# IOB-Adapter-Generic.net
KiCad netlist of a schematic drawn in EAGLE
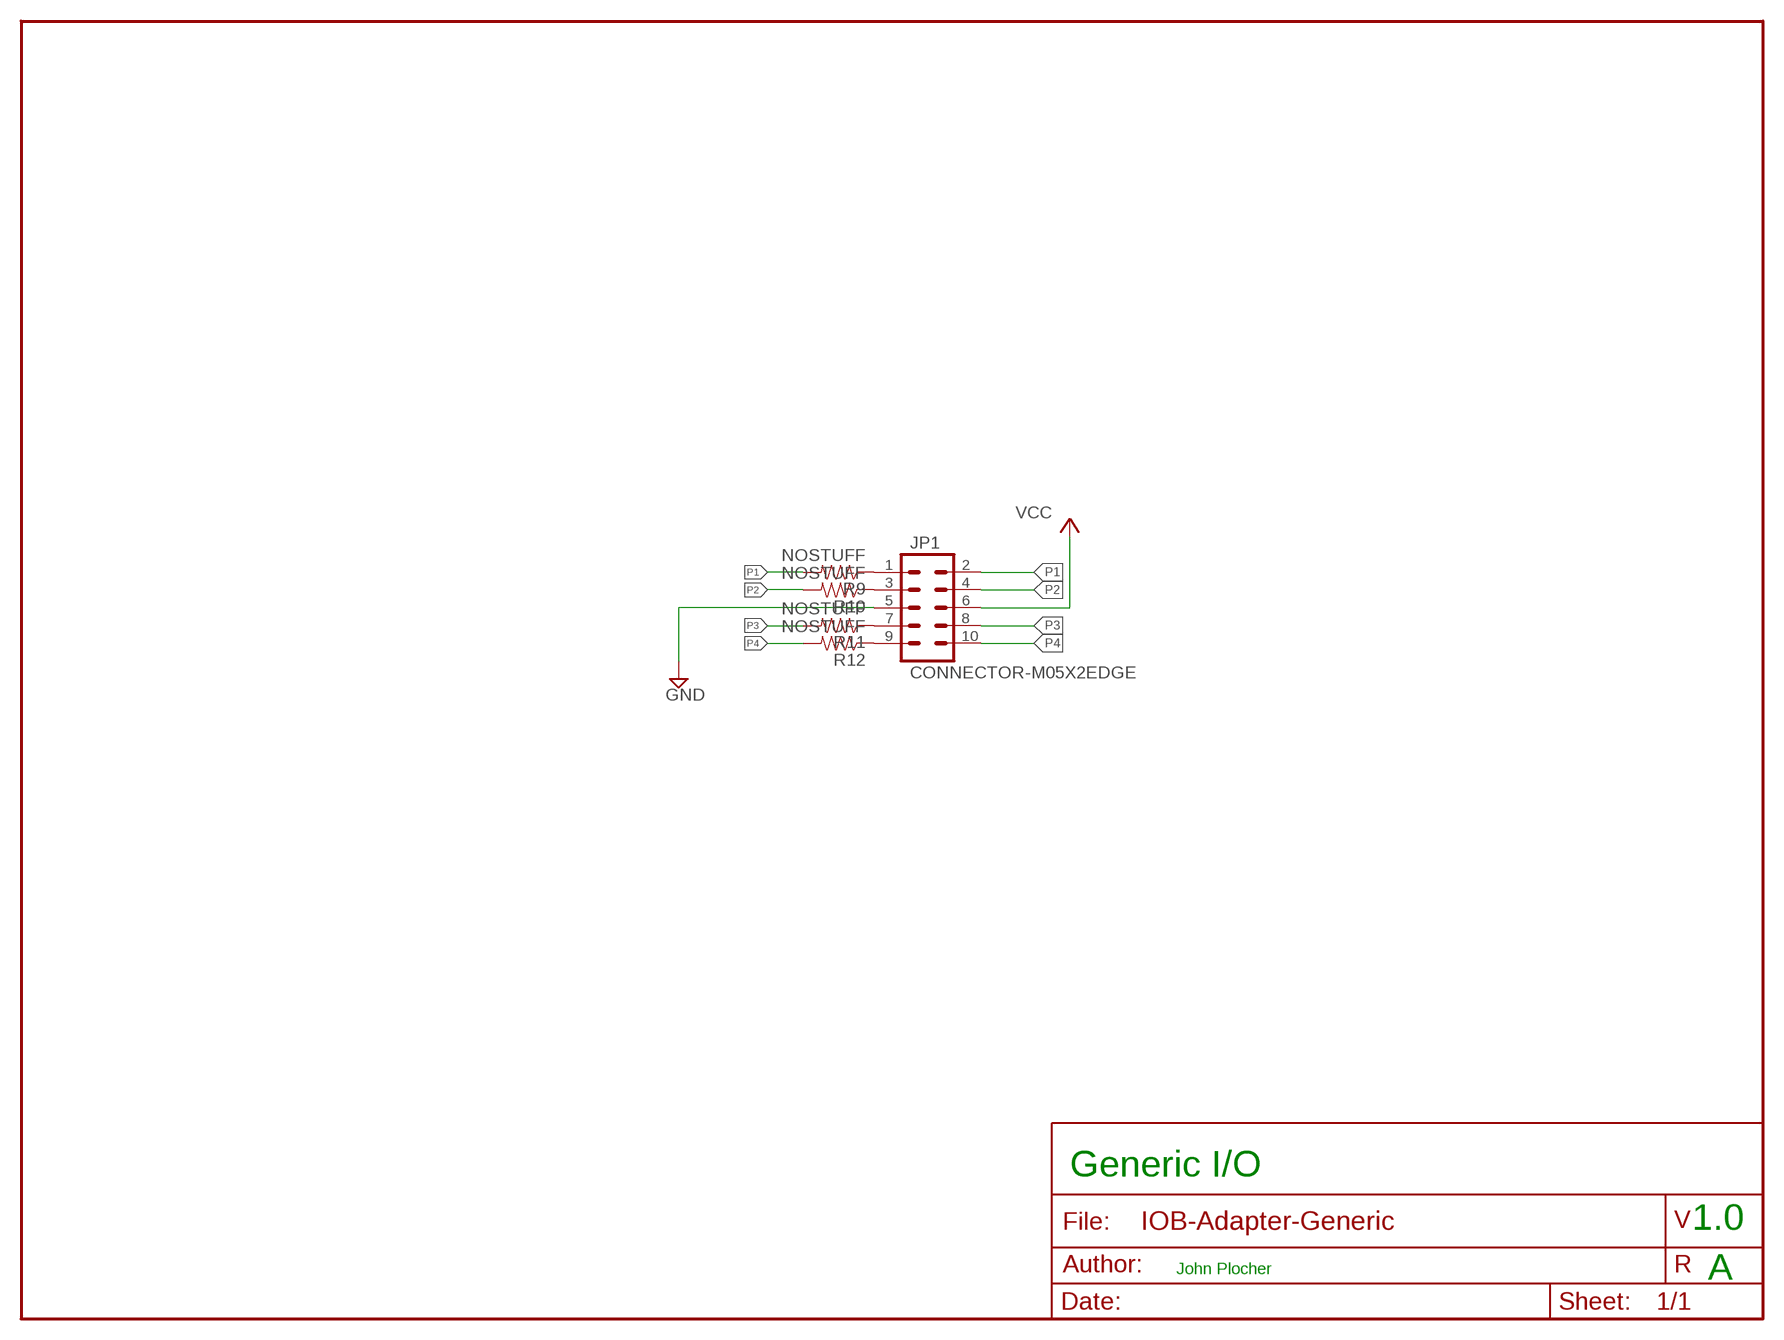
[diagram p0: schematic, sheet 1]

(export (version "E")
  (design (tool "Eeschema 10.0.6"))
  (components
    (comp (ref "JP1")
      (value "CONNECTOR-M05X2EDGE")
      (footprint "eagle-import:2X5-EDGE")
      (libsource (lib "eagle-import") (part "CONNECTOR-M05X2EDGE"))
    )
    (comp (ref "R9")
      (value "NOSTUFF")
      (footprint "eagle-import:CUT-R")
      (libsource (lib "eagle-import") (part "RPTH-R0"))
    )
    (comp (ref "R10")
      (value "NOSTUFF")
      (footprint "eagle-import:CUT-R")
      (libsource (lib "eagle-import") (part "RPTH-R0"))
    )
    (comp (ref "R11")
      (value "NOSTUFF")
      (footprint "eagle-import:CUT-R")
      (libsource (lib "eagle-import") (part "RPTH-R0"))
    )
    (comp (ref "R12")
      (value "NOSTUFF")
      (footprint "eagle-import:CUT-R")
      (libsource (lib "eagle-import") (part "RPTH-R0"))
    )
  )
  (nets
    (net (code "1") (name "GND") (class "Default")
      (node (ref "JP1") (pin "5") (pinfunction "5_5") (pintype "passive"))
    )
    (net (code "2") (name "Net-(R9-1)") (class "Default")
      (node (ref "JP1") (pin "1") (pinfunction "1_1") (pintype "passive"))
      (node (ref "R9") (pin "P2") (pinfunction "1_P2") (pintype "passive"))
    )
    (net (code "3") (name "Net-(R10-1)") (class "Default")
      (node (ref "JP1") (pin "3") (pinfunction "3_3") (pintype "passive"))
      (node (ref "R10") (pin "P2") (pinfunction "1_P2") (pintype "passive"))
    )
    (net (code "4") (name "Net-(R11-1)") (class "Default")
      (node (ref "JP1") (pin "7") (pinfunction "7_7") (pintype "passive"))
      (node (ref "R11") (pin "P2") (pinfunction "1_P2") (pintype "passive"))
    )
    (net (code "5") (name "Net-(R12-1)") (class "Default")
      (node (ref "JP1") (pin "9") (pinfunction "9_9") (pintype "passive"))
      (node (ref "R12") (pin "P2") (pinfunction "1_P2") (pintype "passive"))
    )
    (net (code "6") (name "P1") (class "Default")
      (node (ref "JP1") (pin "2") (pinfunction "2_2") (pintype "passive"))
      (node (ref "R9") (pin "P1") (pinfunction "2_P1") (pintype "passive"))
    )
    (net (code "7") (name "P2") (class "Default")
      (node (ref "JP1") (pin "4") (pinfunction "4_4") (pintype "passive"))
      (node (ref "R10") (pin "P1") (pinfunction "2_P1") (pintype "passive"))
    )
    (net (code "8") (name "P3") (class "Default")
      (node (ref "JP1") (pin "8") (pinfunction "8_8") (pintype "passive"))
      (node (ref "R11") (pin "P1") (pinfunction "2_P1") (pintype "passive"))
    )
    (net (code "9") (name "P4") (class "Default")
      (node (ref "JP1") (pin "10") (pinfunction "10_10") (pintype "passive"))
      (node (ref "R12") (pin "P1") (pinfunction "2_P1") (pintype "passive"))
    )
    (net (code "10") (name "VCC") (class "Default")
      (node (ref "JP1") (pin "6") (pinfunction "6_6") (pintype "passive"))
    )
  )
)
